# Sheet1.net
KiCad netlist of a schematic drawn in Altium Designer
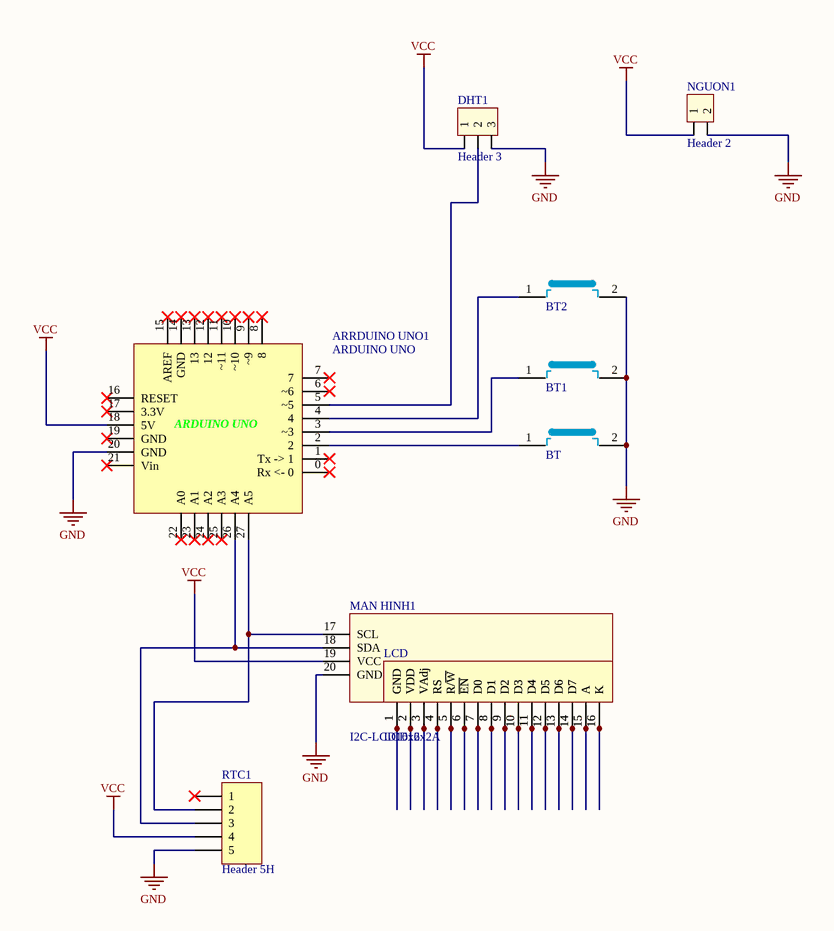
[diagram p0: Sheet1.SchDoc]

(export (version "E")
  (design (tool "Eeschema 10.0.6"))
  (components
    (comp (ref "ARRDUINO UNO1")
      (value "ARDUINO UNO")
      (footprint "ARDUINO UNO")
      (libsource (lib "My library altium") (part "ARDUINO UNO"))
    )
    (comp (ref "BT1") (value "BT2") (footprint "SW4") (libsource (lib "My library altium") (part "BUTTON")))
    (comp (ref "BT2") (value "BT1") (footprint "SW4") (libsource (lib "My library altium") (part "BUTTON")))
    (comp (ref "BT3") (value "BT") (footprint "SW4") (libsource (lib "My library altium") (part "BUTTON")))
    (comp (ref "DHT1")
      (value "Header 3")
      (footprint "HED3")
      (description "Header 3 (Green)")
      (libsource (lib "syhaunguyen") (part "Hed3"))
    )
    (comp (ref "LCD")
      (value "LCD16x2A")
      (footprint "LCD16X2")
      (description "LCD dipslay 16 char, 2 line")
      (libsource (lib "My library altium") (part "LCD16x2"))
    )
    (comp (ref "MAN HINH1")
      (value "I2C-LCD16x2")
      (footprint "I2C-LCD16X2")
      (description "LCD dipslay 16 char, 2 line")
      (libsource (lib "My library altium") (part "I2C-LCD16x2"))
    )
    (comp (ref "NGUON1")
      (value "Header 2")
      (footprint "HED2")
      (description "Header 2 (Green)")
      (libsource (lib "My library altium") (part "Header 2"))
    )
    (comp (ref "RTC1")
      (value "Header 5H")
      (footprint "HDR1X5H")
      (description "Header, 5-Pin, Right Angle")
      (fields (field (name "PUBLISHER") "Altium Limited"))
      (libsource (lib "My library altium") (part "Header 5H"))
    )
  )
  (nets
    (net (code "1") (name "GND") (class "Default")
      (node (ref "ARRDUINO UNO1") (pin "20") (pinfunction "GND_20") (pintype "passive"))
      (node (ref "BT1") (pin "2") (pinfunction "2_2") (pintype "passive"))
      (node (ref "BT2") (pin "2") (pinfunction "2_2") (pintype "passive"))
      (node (ref "BT3") (pin "2") (pinfunction "2_2") (pintype "passive"))
      (node (ref "DHT1") (pin "3") (pinfunction "3_3") (pintype "passive"))
      (node (ref "MAN HINH1") (pin "20") (pinfunction "GND_20") (pintype "passive"))
      (node (ref "NGUON1") (pin "2") (pinfunction "2_2") (pintype "passive"))
      (node (ref "RTC1") (pin "5") (pinfunction "5_5") (pintype "passive"))
    )
    (net (code "2") (name "Net-(ARRDUINO UNO1-A4)") (class "Default")
      (node (ref "ARRDUINO UNO1") (pin "26") (pinfunction "A4_26") (pintype "passive"))
      (node (ref "MAN HINH1") (pin "18") (pinfunction "SDA_18") (pintype "passive"))
      (node (ref "RTC1") (pin "3") (pinfunction "3_3") (pintype "passive"))
    )
    (net (code "3") (name "Net-(ARRDUINO UNO1-A5)") (class "Default")
      (node (ref "ARRDUINO UNO1") (pin "27") (pinfunction "A5_27") (pintype "passive"))
      (node (ref "MAN HINH1") (pin "17") (pinfunction "SCL_17") (pintype "passive"))
      (node (ref "RTC1") (pin "2") (pinfunction "2_2") (pintype "passive"))
    )
    (net (code "4") (name "Net-(ARRDUINO UNO1-Pad2)") (class "Default")
      (node (ref "ARRDUINO UNO1") (pin "2") (pinfunction "2_2") (pintype "passive"))
      (node (ref "BT3") (pin "1") (pinfunction "1_1") (pintype "passive"))
    )
    (net (code "5") (name "Net-(ARRDUINO UNO1-Pad4)") (class "Default")
      (node (ref "ARRDUINO UNO1") (pin "4") (pinfunction "4_4") (pintype "passive"))
      (node (ref "BT1") (pin "1") (pinfunction "1_1") (pintype "passive"))
    )
    (net (code "6") (name "Net-(ARRDUINO UNO1-~3)") (class "Default")
      (node (ref "ARRDUINO UNO1") (pin "3") (pinfunction "~3_3") (pintype "passive"))
      (node (ref "BT2") (pin "1") (pinfunction "1_1") (pintype "passive"))
    )
    (net (code "7") (name "Net-(ARRDUINO UNO1-~5)") (class "Default")
      (node (ref "ARRDUINO UNO1") (pin "5") (pinfunction "~5_5") (pintype "passive"))
      (node (ref "DHT1") (pin "2") (pinfunction "2_2") (pintype "passive"))
    )
    (net (code "8") (name "Net-(LCD-A)") (class "Default")
      (node (ref "LCD") (pin "15") (pinfunction "A_15") (pintype "passive"))
      (node (ref "MAN HINH1") (pin "15") (pinfunction "A_15") (pintype "passive"))
    )
    (net (code "9") (name "Net-(LCD-D0)") (class "Default")
      (node (ref "LCD") (pin "7") (pinfunction "D0_7") (pintype "passive"))
      (node (ref "MAN HINH1") (pin "7") (pinfunction "D0_7") (pintype "passive"))
    )
    (net (code "10") (name "Net-(LCD-D1)") (class "Default")
      (node (ref "LCD") (pin "8") (pinfunction "D1_8") (pintype "passive"))
      (node (ref "MAN HINH1") (pin "8") (pinfunction "D1_8") (pintype "passive"))
    )
    (net (code "11") (name "Net-(LCD-D2)") (class "Default")
      (node (ref "LCD") (pin "9") (pinfunction "D2_9") (pintype "passive"))
      (node (ref "MAN HINH1") (pin "9") (pinfunction "D2_9") (pintype "passive"))
    )
    (net (code "12") (name "Net-(LCD-D3)") (class "Default")
      (node (ref "LCD") (pin "10") (pinfunction "D3_10") (pintype "passive"))
      (node (ref "MAN HINH1") (pin "10") (pinfunction "D3_10") (pintype "passive"))
    )
    (net (code "13") (name "Net-(LCD-D4)") (class "Default")
      (node (ref "LCD") (pin "11") (pinfunction "D4_11") (pintype "passive"))
      (node (ref "MAN HINH1") (pin "11") (pinfunction "D4_11") (pintype "passive"))
    )
    (net (code "14") (name "Net-(LCD-D5)") (class "Default")
      (node (ref "LCD") (pin "12") (pinfunction "D5_12") (pintype "passive"))
      (node (ref "MAN HINH1") (pin "12") (pinfunction "D5_12") (pintype "passive"))
    )
    (net (code "15") (name "Net-(LCD-D6)") (class "Default")
      (node (ref "LCD") (pin "13") (pinfunction "D6_13") (pintype "passive"))
      (node (ref "MAN HINH1") (pin "13") (pinfunction "D6_13") (pintype "passive"))
    )
    (net (code "16") (name "Net-(LCD-D7)") (class "Default")
      (node (ref "LCD") (pin "14") (pinfunction "D7_14") (pintype "passive"))
      (node (ref "MAN HINH1") (pin "14") (pinfunction "D7_14") (pintype "passive"))
    )
    (net (code "17") (name "Net-(LCD-GND)") (class "Default")
      (node (ref "LCD") (pin "1") (pinfunction "GND_1") (pintype "passive"))
      (node (ref "MAN HINH1") (pin "1") (pinfunction "GND_1") (pintype "passive"))
    )
    (net (code "18") (name "Net-(LCD-K)") (class "Default")
      (node (ref "LCD") (pin "16") (pinfunction "K_16") (pintype "passive"))
      (node (ref "MAN HINH1") (pin "16") (pinfunction "K_16") (pintype "passive"))
    )
    (net (code "19") (name "Net-(LCD-RS)") (class "Default")
      (node (ref "LCD") (pin "4") (pinfunction "RS_4") (pintype "passive"))
      (node (ref "MAN HINH1") (pin "4") (pinfunction "RS_4") (pintype "passive"))
    )
    (net (code "20") (name "Net-(LCD-R{slash}~{W})") (class "Default")
      (node (ref "LCD") (pin "5") (pinfunction "R/~{W}_5") (pintype "passive"))
      (node (ref "MAN HINH1") (pin "5") (pinfunction "R/~{W}_5") (pintype "passive"))
    )
    (net (code "21") (name "Net-(LCD-VAdj)") (class "Default")
      (node (ref "LCD") (pin "3") (pinfunction "VAdj_3") (pintype "passive"))
      (node (ref "MAN HINH1") (pin "3") (pinfunction "VAdj_3") (pintype "passive"))
    )
    (net (code "22") (name "Net-(LCD-VDD)") (class "Default")
      (node (ref "LCD") (pin "2") (pinfunction "VDD_2") (pintype "passive"))
      (node (ref "MAN HINH1") (pin "2") (pinfunction "VDD_2") (pintype "passive"))
    )
    (net (code "23") (name "Net-(LCD-~{EN})") (class "Default")
      (node (ref "LCD") (pin "6") (pinfunction "~{EN}_6") (pintype "passive"))
      (node (ref "MAN HINH1") (pin "6") (pinfunction "~{EN}_6") (pintype "passive"))
    )
    (net (code "24") (name "VCC") (class "Default")
      (node (ref "ARRDUINO UNO1") (pin "18") (pinfunction "5V_18") (pintype "passive"))
      (node (ref "DHT1") (pin "1") (pinfunction "1_1") (pintype "passive"))
      (node (ref "MAN HINH1") (pin "19") (pinfunction "VCC_19") (pintype "passive"))
      (node (ref "NGUON1") (pin "1") (pinfunction "1_1") (pintype "passive"))
      (node (ref "RTC1") (pin "4") (pinfunction "4_4") (pintype "passive"))
    )
    (net (code "25") (name "unconnected-(ARRDUINO UNO1-3.3V-Pad17)") (class "Default")
      (node (ref "ARRDUINO UNO1") (pin "17") (pinfunction "3.3V_17") (pintype "passive+no_connect"))
    )
    (net (code "26") (name "unconnected-(ARRDUINO UNO1-A0-Pad22)") (class "Default")
      (node (ref "ARRDUINO UNO1") (pin "22") (pinfunction "A0_22") (pintype "passive+no_connect"))
    )
    (net (code "27") (name "unconnected-(ARRDUINO UNO1-A1-Pad23)") (class "Default")
      (node (ref "ARRDUINO UNO1") (pin "23") (pinfunction "A1_23") (pintype "passive+no_connect"))
    )
    (net (code "28") (name "unconnected-(ARRDUINO UNO1-A2-Pad24)") (class "Default")
      (node (ref "ARRDUINO UNO1") (pin "24") (pinfunction "A2_24") (pintype "passive+no_connect"))
    )
    (net (code "29") (name "unconnected-(ARRDUINO UNO1-A3-Pad25)") (class "Default")
      (node (ref "ARRDUINO UNO1") (pin "25") (pinfunction "A3_25") (pintype "passive+no_connect"))
    )
    (net (code "30") (name "unconnected-(ARRDUINO UNO1-AREF-Pad15)") (class "Default")
      (node (ref "ARRDUINO UNO1") (pin "15") (pinfunction "AREF_15") (pintype "passive+no_connect"))
    )
    (net (code "31") (name "unconnected-(ARRDUINO UNO1-GND-Pad14)") (class "Default")
      (node (ref "ARRDUINO UNO1") (pin "14") (pinfunction "GND_14") (pintype "passive+no_connect"))
    )
    (net (code "32") (name "unconnected-(ARRDUINO UNO1-GND-Pad19)") (class "Default")
      (node (ref "ARRDUINO UNO1") (pin "19") (pinfunction "GND_19") (pintype "passive+no_connect"))
    )
    (net (code "33") (name "unconnected-(ARRDUINO UNO1-Pad7)") (class "Default")
      (node (ref "ARRDUINO UNO1") (pin "7") (pinfunction "7_7") (pintype "passive+no_connect"))
    )
    (net (code "34") (name "unconnected-(ARRDUINO UNO1-Pad8)") (class "Default")
      (node (ref "ARRDUINO UNO1") (pin "8") (pinfunction "8_8") (pintype "passive+no_connect"))
    )
    (net (code "35") (name "unconnected-(ARRDUINO UNO1-Pad12)") (class "Default")
      (node (ref "ARRDUINO UNO1") (pin "12") (pinfunction "12_12") (pintype "passive+no_connect"))
    )
    (net (code "36") (name "unconnected-(ARRDUINO UNO1-Pad13)") (class "Default")
      (node (ref "ARRDUINO UNO1") (pin "13") (pinfunction "13_13") (pintype "passive+no_connect"))
    )
    (net (code "37") (name "unconnected-(ARRDUINO UNO1-RESET-Pad16)") (class "Default")
      (node (ref "ARRDUINO UNO1") (pin "16") (pinfunction "RESET_16") (pintype "passive+no_connect"))
    )
    (net (code "38") (name "unconnected-(ARRDUINO UNO1-Rx_<-_0-Pad0)") (class "Default")
      (node (ref "ARRDUINO UNO1") (pin "0") (pinfunction "Rx_<-_0_0") (pintype "passive+no_connect"))
    )
    (net (code "39") (name "unconnected-(ARRDUINO UNO1-Tx_->_1-Pad1)") (class "Default")
      (node (ref "ARRDUINO UNO1") (pin "1") (pinfunction "Tx_->_1_1") (pintype "passive+no_connect"))
    )
    (net (code "40") (name "unconnected-(ARRDUINO UNO1-Vin-Pad21)") (class "Default")
      (node (ref "ARRDUINO UNO1") (pin "21") (pinfunction "Vin_21") (pintype "passive+no_connect"))
    )
    (net (code "41") (name "unconnected-(ARRDUINO UNO1-~6-Pad6)") (class "Default")
      (node (ref "ARRDUINO UNO1") (pin "6") (pinfunction "~6_6") (pintype "passive+no_connect"))
    )
    (net (code "42") (name "unconnected-(ARRDUINO UNO1-~9-Pad9)") (class "Default")
      (node (ref "ARRDUINO UNO1") (pin "9") (pinfunction "~9_9") (pintype "passive+no_connect"))
    )
    (net (code "43") (name "unconnected-(ARRDUINO UNO1-~10-Pad10)") (class "Default")
      (node (ref "ARRDUINO UNO1") (pin "10") (pinfunction "~10_10") (pintype "passive+no_connect"))
    )
    (net (code "44") (name "unconnected-(ARRDUINO UNO1-~11-Pad11)") (class "Default")
      (node (ref "ARRDUINO UNO1") (pin "11") (pinfunction "~11_11") (pintype "passive+no_connect"))
    )
    (net (code "45") (name "unconnected-(RTC1-Pad1)") (class "Default")
      (node (ref "RTC1") (pin "1") (pinfunction "1_1") (pintype "passive+no_connect"))
    )
  )
)
